# Main.net
KiCad netlist of a schematic drawn in Altium Designer
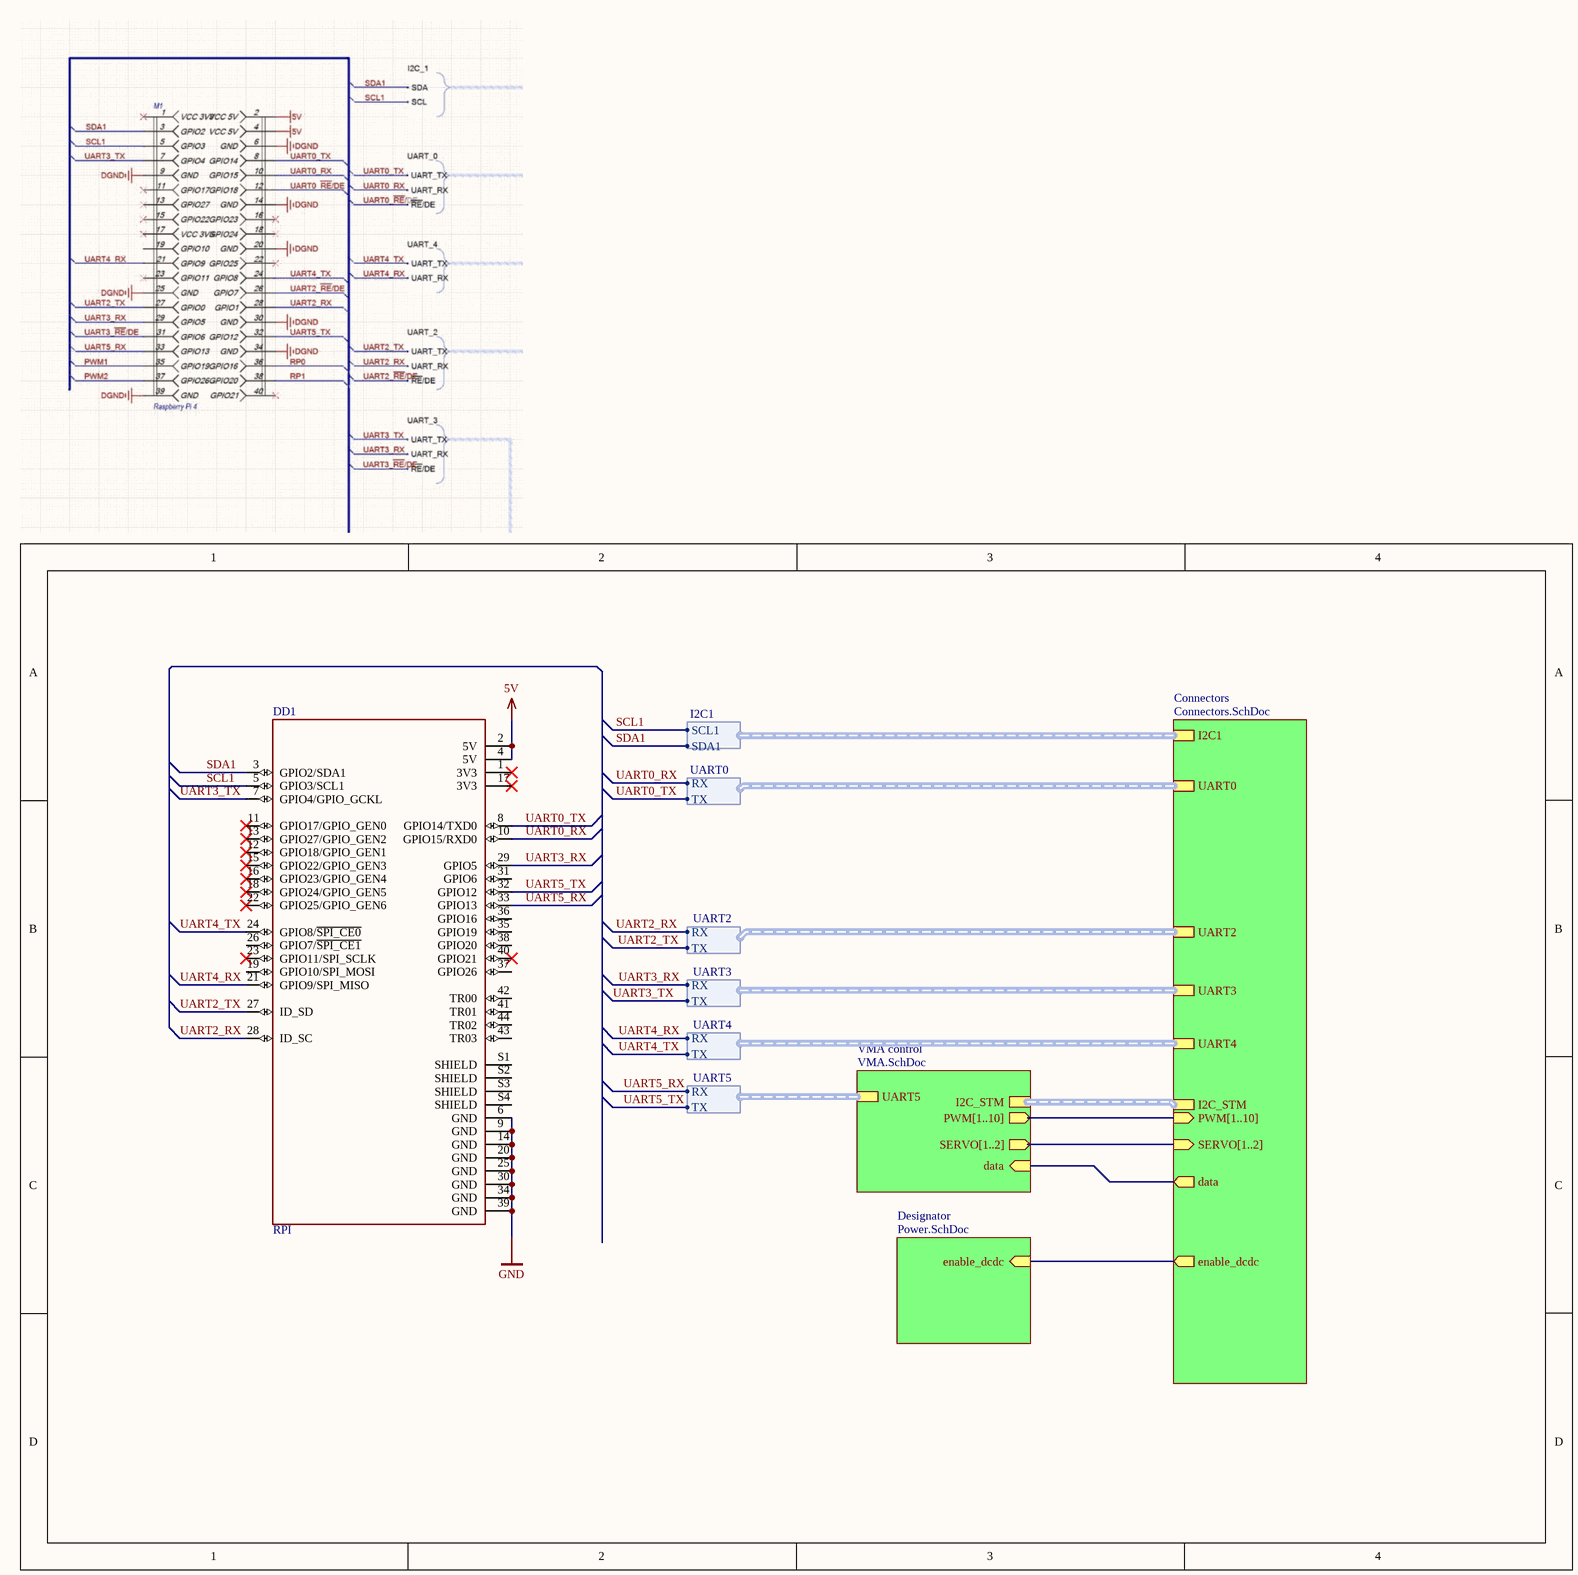
[diagram p0: Main.SchDoc]

(export (version "E")
  (design (tool "Eeschema 10.0.6"))
  (components (comp (ref "DD1") (value "RPI") (footprint "RPI") (libsource (lib "Hydrolib") (part "RPI"))))
  (nets
    (net (code "9") (name "/SCL1") (class "Default")
      (node (ref "DD1") (pin "5") (pinfunction "GPIO3/SCL1_5") (pintype "bidirectional"))
    )
    (net (code "10") (name "/SDA1") (class "Default")
      (node (ref "DD1") (pin "3") (pinfunction "GPIO2/SDA1_3") (pintype "bidirectional"))
    )
    (net (code "12") (name "/UART0_RX") (class "Default")
      (node (ref "DD1") (pin "10") (pinfunction "GPIO15/RXD0_10") (pintype "bidirectional"))
    )
    (net (code "13") (name "/UART0_TX") (class "Default")
      (node (ref "DD1") (pin "8") (pinfunction "GPIO14/TXD0_8") (pintype "bidirectional"))
    )
    (net (code "14") (name "/UART2_RX") (class "Default")
      (node (ref "DD1") (pin "28") (pinfunction "ID_SC_28") (pintype "bidirectional"))
    )
    (net (code "15") (name "/UART2_TX") (class "Default")
      (node (ref "DD1") (pin "27") (pinfunction "ID_SD_27") (pintype "bidirectional"))
    )
    (net (code "16") (name "/UART3_RX") (class "Default")
      (node (ref "DD1") (pin "29") (pinfunction "GPIO5_29") (pintype "bidirectional"))
    )
    (net (code "17") (name "/UART3_TX") (class "Default")
      (node (ref "DD1") (pin "7") (pinfunction "GPIO4/GPIO_GCKL_7") (pintype "bidirectional"))
    )
    (net (code "18") (name "/UART4_RX") (class "Default")
      (node (ref "DD1") (pin "21") (pinfunction "GPIO9/SPI_MISO_21") (pintype "bidirectional"))
    )
    (net (code "19") (name "/UART4_TX") (class "Default")
      (node (ref "DD1") (pin "24") (pinfunction "GPIO8/~{SPI_CE0}_24") (pintype "bidirectional"))
    )
    (net (code "20") (name "/UART5_RX") (class "Default")
      (node (ref "DD1") (pin "33") (pinfunction "GPIO13_33") (pintype "bidirectional"))
    )
    (net (code "21") (name "/UART5_TX") (class "Default")
      (node (ref "DD1") (pin "32") (pinfunction "GPIO12_32") (pintype "bidirectional"))
    )
    (net (code "30") (name "5V") (class "Default")
      (node (ref "DD1") (pin "2") (pinfunction "5V_2") (pintype "power_in"))
      (node (ref "DD1") (pin "4") (pinfunction "5V_4") (pintype "power_in"))
    )
    (net (code "31") (name "GND") (class "Default")
      (node (ref "DD1") (pin "14") (pinfunction "GND_14") (pintype "power_in"))
      (node (ref "DD1") (pin "20") (pinfunction "GND_20") (pintype "power_in"))
      (node (ref "DD1") (pin "25") (pinfunction "GND_25") (pintype "power_in"))
      (node (ref "DD1") (pin "30") (pinfunction "GND_30") (pintype "power_in"))
      (node (ref "DD1") (pin "34") (pinfunction "GND_34") (pintype "power_in"))
      (node (ref "DD1") (pin "39") (pinfunction "GND_39") (pintype "power_in"))
      (node (ref "DD1") (pin "6") (pinfunction "GND_6") (pintype "power_in"))
      (node (ref "DD1") (pin "9") (pinfunction "GND_9") (pintype "power_in"))
    )
    (net (code "32") (name "unconnected-(DD1-3V3-Pad1)") (class "Default")
      (node (ref "DD1") (pin "1") (pinfunction "3V3_1") (pintype "power_in+no_connect"))
    )
    (net (code "33") (name "unconnected-(DD1-3V3-Pad17)") (class "Default")
      (node (ref "DD1") (pin "17") (pinfunction "3V3_17") (pintype "power_in+no_connect"))
    )
    (net (code "34") (name "unconnected-(DD1-GPIO6-Pad31)") (class "Default")
      (node (ref "DD1") (pin "31") (pinfunction "GPIO6_31") (pintype "bidirectional"))
    )
    (net (code "35") (name "unconnected-(DD1-GPIO7{slash}~{SPI_CE1}-Pad26)") (class "Default")
      (node (ref "DD1") (pin "26") (pinfunction "GPIO7/~{SPI_CE1}_26") (pintype "bidirectional"))
    )
    (net (code "36") (name "unconnected-(DD1-GPIO10{slash}SPI_MOSI-Pad19)") (class "Default")
      (node (ref "DD1") (pin "19") (pinfunction "GPIO10/SPI_MOSI_19") (pintype "bidirectional"))
    )
    (net (code "37") (name "unconnected-(DD1-GPIO11{slash}SPI_SCLK-Pad23)") (class "Default")
      (node (ref "DD1") (pin "23") (pinfunction "GPIO11/SPI_SCLK_23") (pintype "bidirectional+no_connect"))
    )
    (net (code "38") (name "unconnected-(DD1-GPIO16-Pad36)") (class "Default")
      (node (ref "DD1") (pin "36") (pinfunction "GPIO16_36") (pintype "bidirectional"))
    )
    (net (code "39") (name "unconnected-(DD1-GPIO17{slash}GPIO_GEN0-Pad11)") (class "Default")
      (node (ref "DD1") (pin "11") (pinfunction "GPIO17/GPIO_GEN0_11") (pintype "bidirectional+no_connect"))
    )
    (net (code "40") (name "unconnected-(DD1-GPIO18{slash}GPIO_GEN1-Pad12)") (class "Default")
      (node (ref "DD1") (pin "12") (pinfunction "GPIO18/GPIO_GEN1_12") (pintype "bidirectional+no_connect"))
    )
    (net (code "41") (name "unconnected-(DD1-GPIO19-Pad35)") (class "Default")
      (node (ref "DD1") (pin "35") (pinfunction "GPIO19_35") (pintype "bidirectional"))
    )
    (net (code "42") (name "unconnected-(DD1-GPIO20-Pad38)") (class "Default")
      (node (ref "DD1") (pin "38") (pinfunction "GPIO20_38") (pintype "bidirectional"))
    )
    (net (code "43") (name "unconnected-(DD1-GPIO21-Pad40)") (class "Default")
      (node (ref "DD1") (pin "40") (pinfunction "GPIO21_40") (pintype "bidirectional+no_connect"))
    )
    (net (code "44") (name "unconnected-(DD1-GPIO22{slash}GPIO_GEN3-Pad15)") (class "Default")
      (node (ref "DD1") (pin "15") (pinfunction "GPIO22/GPIO_GEN3_15") (pintype "bidirectional+no_connect"))
    )
    (net (code "45") (name "unconnected-(DD1-GPIO23{slash}GPIO_GEN4-Pad16)") (class "Default")
      (node (ref "DD1") (pin "16") (pinfunction "GPIO23/GPIO_GEN4_16") (pintype "bidirectional+no_connect"))
    )
    (net (code "46") (name "unconnected-(DD1-GPIO24{slash}GPIO_GEN5-Pad18)") (class "Default")
      (node (ref "DD1") (pin "18") (pinfunction "GPIO24/GPIO_GEN5_18") (pintype "bidirectional+no_connect"))
    )
    (net (code "47") (name "unconnected-(DD1-GPIO25{slash}GPIO_GEN6-Pad22)") (class "Default")
      (node (ref "DD1") (pin "22") (pinfunction "GPIO25/GPIO_GEN6_22") (pintype "bidirectional+no_connect"))
    )
    (net (code "48") (name "unconnected-(DD1-GPIO26-Pad37)") (class "Default")
      (node (ref "DD1") (pin "37") (pinfunction "GPIO26_37") (pintype "bidirectional"))
    )
    (net (code "49") (name "unconnected-(DD1-GPIO27{slash}GPIO_GEN2-Pad13)") (class "Default")
      (node (ref "DD1") (pin "13") (pinfunction "GPIO27/GPIO_GEN2_13") (pintype "bidirectional+no_connect"))
    )
    (net (code "50") (name "unconnected-(DD1-SHIELD-PadS1)") (class "Default")
      (node (ref "DD1") (pin "S1") (pinfunction "SHIELD_S1") (pintype "power_in"))
    )
    (net (code "51") (name "unconnected-(DD1-SHIELD-PadS2)") (class "Default")
      (node (ref "DD1") (pin "S2") (pinfunction "SHIELD_S2") (pintype "power_in"))
    )
    (net (code "52") (name "unconnected-(DD1-SHIELD-PadS3)") (class "Default")
      (node (ref "DD1") (pin "S3") (pinfunction "SHIELD_S3") (pintype "power_in"))
    )
    (net (code "53") (name "unconnected-(DD1-SHIELD-PadS4)") (class "Default")
      (node (ref "DD1") (pin "S4") (pinfunction "SHIELD_S4") (pintype "power_in"))
    )
    (net (code "54") (name "unconnected-(DD1-TR00-Pad42)") (class "Default")
      (node (ref "DD1") (pin "42") (pinfunction "TR00_42") (pintype "bidirectional"))
    )
    (net (code "55") (name "unconnected-(DD1-TR01-Pad41)") (class "Default")
      (node (ref "DD1") (pin "41") (pinfunction "TR01_41") (pintype "bidirectional"))
    )
    (net (code "56") (name "unconnected-(DD1-TR02-Pad44)") (class "Default")
      (node (ref "DD1") (pin "44") (pinfunction "TR02_44") (pintype "bidirectional"))
    )
    (net (code "57") (name "unconnected-(DD1-TR03-Pad43)") (class "Default")
      (node (ref "DD1") (pin "43") (pinfunction "TR03_43") (pintype "bidirectional"))
    )
  )
)
